# 7_ALARM.net
KiCad netlist of a schematic drawn in Altium Designer
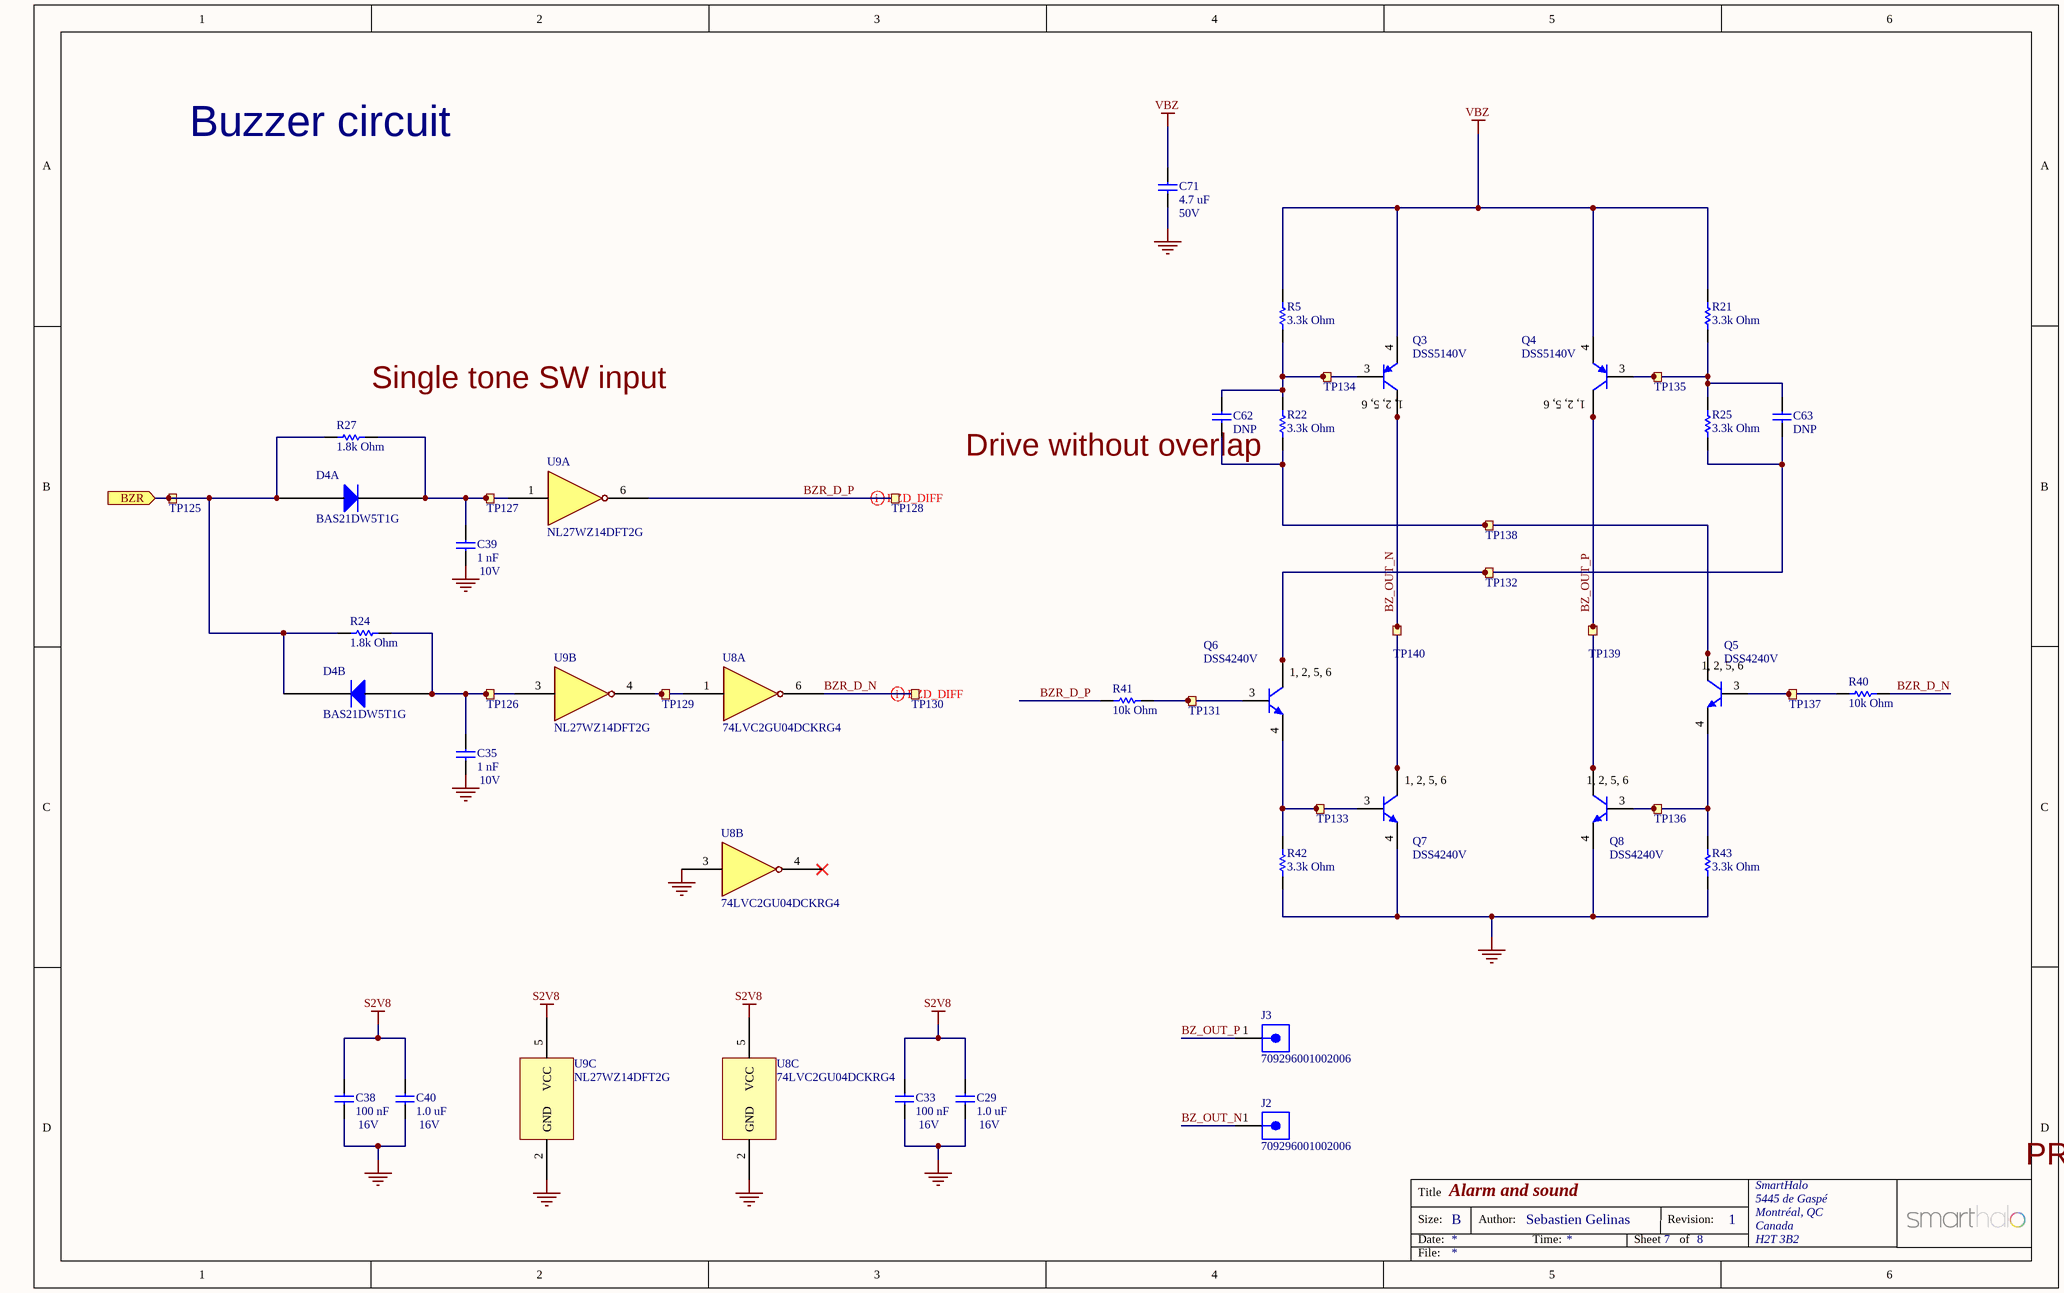
[diagram p0: 7_ALARM.SchDoc]

(export (version "E")
  (design (tool "Eeschema 10.0.6"))
  (components
    (comp (ref "C29")
      (value "1.0 uF")
      (footprint "Varitron_CAP0603")
      (description "1.0 uF 16V X7R 10% 0603 (1608 Metric)  SMD")
      (fields
        (field (name "TOLERANCE") "10%")
        (field (name "VOLTAGE RATING") "16V")
        (field (name "MANUFACTURER") "Samsung")
      )
      (libsource (lib "SmartHalo") (part "Varitron_CAP0603"))
    )
    (comp (ref "C33")
      (value "100 nF")
      (footprint "Varitron_CAP0402")
      (description "100 nF 16V X7R 10% 0402 (1005 Metric)  SMD")
      (fields
        (field (name "TOLERANCE") "10%")
        (field (name "VOLTAGE RATING") "16V")
        (field (name "MANUFACTURER") "Samsung")
      )
      (libsource (lib "SmartHalo") (part "Varitron_CAP0402"))
    )
    (comp (ref "C35")
      (value "1 nF")
      (footprint "Varitron_CAP0402")
      (description "1 nF 10V X7R 10% 0402 (1005 Metric)  SMD")
      (fields
        (field (name "TOLERANCE") "10%")
        (field (name "VOLTAGE RATING") "10V")
        (field (name "MANUFACTURER") "AVX")
      )
      (libsource (lib "SmartHalo") (part "Varitron_CAP0402"))
    )
    (comp (ref "C38")
      (value "100 nF")
      (footprint "Varitron_CAP0402")
      (description "100 nF 16V X7R 10% 0402 (1005 Metric)  SMD")
      (fields
        (field (name "TOLERANCE") "10%")
        (field (name "VOLTAGE RATING") "16V")
        (field (name "MANUFACTURER") "Samsung")
      )
      (libsource (lib "SmartHalo") (part "Varitron_CAP0402"))
    )
    (comp (ref "C39")
      (value "1 nF")
      (footprint "Varitron_CAP0402")
      (description "1 nF 10V X7R 10% 0402 (1005 Metric)  SMD")
      (fields
        (field (name "TOLERANCE") "10%")
        (field (name "VOLTAGE RATING") "10V")
        (field (name "MANUFACTURER") "AVX")
      )
      (libsource (lib "SmartHalo") (part "Varitron_CAP0402"))
    )
    (comp (ref "C40")
      (value "1.0 uF")
      (footprint "Varitron_CAP0603")
      (description "1.0 uF 16V X7R 10% 0603 (1608 Metric)  SMD")
      (fields
        (field (name "TOLERANCE") "10%")
        (field (name "VOLTAGE RATING") "16V")
        (field (name "MANUFACTURER") "Samsung")
      )
      (libsource (lib "SmartHalo") (part "Varitron_CAP0603"))
    )
    (comp (ref "C62")
      (value "DNP")
      (footprint "Varitron_CAP0402")
      (description "220 pF 50V X7R 10% 0402 (1005 Metric)  SMD")
      (fields (field (name "TOLERANCE") "10%"))
      (libsource (lib "SmartHalo") (part "Varitron_CAP0402"))
    )
    (comp (ref "C63")
      (value "DNP")
      (footprint "Varitron_CAP0402")
      (description "220 pF 50V X7R 10% 0402 (1005 Metric)  SMD")
      (fields (field (name "TOLERANCE") "10%"))
      (libsource (lib "SmartHalo") (part "Varitron_CAP0402"))
    )
    (comp (ref "C71")
      (value "4.7 uF")
      (footprint "Varitron_CAP0805")
      (description "4.7 uF 50V X5R 10% 0805 (2012 Metric)  SMD")
      (fields
        (field (name "TOLERANCE") "10%")
        (field (name "MANUFACTURER") "Samsung")
        (field (name "VOLTAGE RATING") "50V")
      )
      (libsource (lib "SmartHalo") (part "Varitron_CAP0805"))
    )
    (comp (ref "D4")
      (value "BAS21DW5T1G")
      (footprint "SC70-5")
      (description "High Voltage Switching Diode")
      (fields
        (field (name "MANUFACTURER") "ON Semiconductor")
        (field (name "SMARTHALO PART NUMBER") "630018-01")
      )
      (libsource (lib "SmartHalo") (part "BAS21DW5T1G"))
    )
    (comp (ref "J2")
      (value "709296001002006")
      (footprint "709296001002006")
      (description "Connector, Single Horizontal Contact, 2 x 2 mm")
      (fields (field (name "MANUFACTURER") "AVX") (field (name "SMARTHALO PART NUMBER") "630020-01"))
      (libsource (lib "SmartHalo") (part "709296001002006"))
    )
    (comp (ref "J3")
      (value "709296001002006")
      (footprint "709296001002006")
      (description "Connector, Single Horizontal Contact, 2 x 2 mm")
      (fields (field (name "MANUFACTURER") "AVX") (field (name "SMARTHALO PART NUMBER") "630020-01"))
      (libsource (lib "SmartHalo") (part "709296001002006"))
    )
    (comp (ref "Q3")
      (value "DSS5140V")
      (footprint "SOT563")
      (description "PNP SMT Transistor, Low VCESAT")
      (fields (field (name "MANUFACTURER") "Diodes Inc.") (field (name "SMARTHALO PART NUMBER") "630031-01"))
      (libsource (lib "SmartHalo") (part "DSS5140V"))
    )
    (comp (ref "Q4")
      (value "DSS5140V")
      (footprint "SOT563")
      (description "PNP SMT Transistor, Low VCESAT")
      (fields (field (name "MANUFACTURER") "Diodes Inc.") (field (name "SMARTHALO PART NUMBER") "630031-01"))
      (libsource (lib "SmartHalo") (part "DSS5140V"))
    )
    (comp (ref "Q5")
      (value "DSS4240V")
      (footprint "SOT563")
      (description "NPN SMT Transistor, Low VCESAT")
      (fields (field (name "MANUFACTURER") "Diodes Inc.") (field (name "SMARTHALO PART NUMBER") "630032-01"))
      (libsource (lib "SmartHalo") (part "DSS4240V"))
    )
    (comp (ref "Q6")
      (value "DSS4240V")
      (footprint "SOT563")
      (description "NPN SMT Transistor, Low VCESAT")
      (fields (field (name "MANUFACTURER") "Diodes Inc.") (field (name "SMARTHALO PART NUMBER") "630032-01"))
      (libsource (lib "SmartHalo") (part "DSS4240V"))
    )
    (comp (ref "Q7")
      (value "DSS4240V")
      (footprint "SOT563")
      (description "NPN SMT Transistor, Low VCESAT")
      (fields (field (name "MANUFACTURER") "Diodes Inc.") (field (name "SMARTHALO PART NUMBER") "630032-01"))
      (libsource (lib "SmartHalo") (part "DSS4240V"))
    )
    (comp (ref "Q8")
      (value "DSS4240V")
      (footprint "SOT563")
      (description "NPN SMT Transistor, Low VCESAT")
      (fields (field (name "MANUFACTURER") "Diodes Inc.") (field (name "SMARTHALO PART NUMBER") "630032-01"))
      (libsource (lib "SmartHalo") (part "DSS4240V"))
    )
    (comp (ref "R5")
      (value "3.3k Ohm")
      (footprint "Varitron_RES0402")
      (description "3k3 0.063W 5%  0402 (1005 Metric)  SMD")
      (fields (field (name "TOLERANCE") "5%") (field (name "POWER") "0.063"))
      (libsource (lib "SmartHalo") (part "Varitron_RES0402"))
    )
    (comp (ref "R21")
      (value "3.3k Ohm")
      (footprint "Varitron_RES0402")
      (description "3k3 0.063W 5%  0402 (1005 Metric)  SMD")
      (fields (field (name "TOLERANCE") "5%") (field (name "POWER") "0.063W"))
      (libsource (lib "SmartHalo") (part "Varitron_RES0402"))
    )
    (comp (ref "R22")
      (value "3.3k Ohm")
      (footprint "Varitron_RES0402")
      (description "3k3 0.063W 5%  0402 (1005 Metric)  SMD")
      (fields (field (name "TOLERANCE") "5%") (field (name "POWER") "0.063W"))
      (libsource (lib "SmartHalo") (part "Varitron_RES0402"))
    )
    (comp (ref "R24")
      (value "1.8k Ohm")
      (footprint "Varitron_RES0402")
      (description "1k8 0.063W 5%  0402 (1005 Metric)  SMD")
      (fields (field (name "TOLERANCE") "5%") (field (name "POWER") "0.063W"))
      (libsource (lib "SmartHalo") (part "Varitron_RES0402"))
    )
    (comp (ref "R25")
      (value "3.3k Ohm")
      (footprint "Varitron_RES0402")
      (description "3k3 0.063W 5%  0402 (1005 Metric)  SMD")
      (fields (field (name "TOLERANCE") "5%") (field (name "POWER") "0.063W"))
      (libsource (lib "SmartHalo") (part "Varitron_RES0402"))
    )
    (comp (ref "R27")
      (value "1.8k Ohm")
      (footprint "Varitron_RES0402")
      (description "1k8 0.063W 5%  0402 (1005 Metric)  SMD")
      (fields (field (name "TOLERANCE") "5%") (field (name "POWER") "0.063W"))
      (libsource (lib "SmartHalo") (part "Varitron_RES0402"))
    )
    (comp (ref "R40")
      (value "10k Ohm")
      (footprint "Varitron_RES0402")
      (description "10k 0.063W 5%  0402 (1005 Metric)  SMD")
      (fields (field (name "TOLERANCE") "5%") (field (name "POWER") "0.063W"))
      (libsource (lib "SmartHalo") (part "Varitron_RES0402"))
    )
    (comp (ref "R41")
      (value "10k Ohm")
      (footprint "Varitron_RES0402")
      (description "10k 0.063W 5%  0402 (1005 Metric)  SMD")
      (fields (field (name "TOLERANCE") "5%") (field (name "POWER") "0.063W"))
      (libsource (lib "SmartHalo") (part "Varitron_RES0402"))
    )
    (comp (ref "R42")
      (value "3.3k Ohm")
      (footprint "Varitron_RES0402")
      (description "3k3 0.063W 5%  0402 (1005 Metric)  SMD")
      (fields (field (name "TOLERANCE") "5%") (field (name "POWER") "0.063W"))
      (libsource (lib "SmartHalo") (part "Varitron_RES0402"))
    )
    (comp (ref "R43")
      (value "3.3k Ohm")
      (footprint "Varitron_RES0402")
      (description "3k3 0.063W 5%  0402 (1005 Metric)  SMD")
      (fields (field (name "TOLERANCE") "5%") (field (name "POWER") "0.063W"))
      (libsource (lib "SmartHalo") (part "Varitron_RES0402"))
    )
    (comp (ref "TP125")
      (value "TP125")
      (footprint "TESTPAD-TH-1_5mm")
      (description "Testpoint, through hole, 1.5mm")
      (libsource (lib "SmartHalo") (part "TESTPAD_TH_1_5MM"))
    )
    (comp (ref "TP126")
      (value "TP126")
      (footprint "TESTPAD-TH-35mils")
      (description "Testpoint, through hole, 35 mils")
      (libsource (lib "SmartHalo") (part "TESTPAD_TH_35mils"))
    )
    (comp (ref "TP127")
      (value "TP127")
      (footprint "TESTPAD-TH-35mils")
      (description "Testpoint, through hole, 35 mils")
      (libsource (lib "SmartHalo") (part "TESTPAD_TH_35mils"))
    )
    (comp (ref "TP128")
      (value "TP128")
      (footprint "TESTPAD-TH-35mils")
      (description "Testpoint, through hole, 35 mils")
      (libsource (lib "SmartHalo") (part "TESTPAD_TH_35mils"))
    )
    (comp (ref "TP129")
      (value "TP129")
      (footprint "TESTPAD-TH-35mils")
      (description "Testpoint, through hole, 35 mils")
      (libsource (lib "SmartHalo") (part "TESTPAD_TH_35mils"))
    )
    (comp (ref "TP130")
      (value "TP130")
      (footprint "TESTPAD-TH-35mils")
      (description "Testpoint, through hole, 35 mils")
      (libsource (lib "SmartHalo") (part "TESTPAD_TH_35mils"))
    )
    (comp (ref "TP131")
      (value "TP131")
      (footprint "TESTPAD-TH-35mils")
      (description "Testpoint, through hole, 35 mils")
      (libsource (lib "SmartHalo") (part "TESTPAD_TH_35mils"))
    )
    (comp (ref "TP132")
      (value "TP132")
      (footprint "TESTPAD-TH-35mils")
      (description "Testpoint, through hole, 35 mils")
      (libsource (lib "SmartHalo") (part "TESTPAD_TH_35mils"))
    )
    (comp (ref "TP133")
      (value "TP133")
      (footprint "TESTPAD-TH-35mils")
      (description "Testpoint, through hole, 35 mils")
      (libsource (lib "SmartHalo") (part "TESTPAD_TH_35mils"))
    )
    (comp (ref "TP134")
      (value "TP134")
      (footprint "TESTPAD-TH-35mils")
      (description "Testpoint, through hole, 35 mils")
      (libsource (lib "SmartHalo") (part "TESTPAD_TH_35mils"))
    )
    (comp (ref "TP135")
      (value "TP135")
      (footprint "TESTPAD-TH-35mils")
      (description "Testpoint, through hole, 35 mils")
      (libsource (lib "SmartHalo") (part "TESTPAD_TH_35mils"))
    )
    (comp (ref "TP136")
      (value "TP136")
      (footprint "TESTPAD-TH-35mils")
      (description "Testpoint, through hole, 35 mils")
      (libsource (lib "SmartHalo") (part "TESTPAD_TH_35mils"))
    )
    (comp (ref "TP137")
      (value "TP137")
      (footprint "TESTPAD-TH-35mils")
      (description "Testpoint, through hole, 35 mils")
      (libsource (lib "SmartHalo") (part "TESTPAD_TH_35mils"))
    )
    (comp (ref "TP138")
      (value "TP138")
      (footprint "TESTPAD-TH-35mils")
      (description "Testpoint, through hole, 35 mils")
      (libsource (lib "SmartHalo") (part "TESTPAD_TH_35mils"))
    )
    (comp (ref "TP139")
      (value "TP139")
      (footprint "TESTPAD-TH-1_5mm")
      (description "Testpoint, through hole, 1.5mm")
      (libsource (lib "") (part "TESTPAD_TH_1_5MM_1"))
    )
    (comp (ref "TP140")
      (value "TP140")
      (footprint "TESTPAD-TH-1_5mm")
      (description "Testpoint, through hole, 1.5mm")
      (libsource (lib "") (part "TESTPAD_TH_1_5MM_1"))
    )
    (comp (ref "U8")
      (value "74LVC2GU04DCKRG4")
      (footprint "SOT363_SC70_6")
      (description "Dual Inverter Gate")
      (fields
        (field (name "MANUFACTURER") "Texas Instruments")
        (field (name "SMARTHALO PART NUMBER") "630057-01")
      )
      (libsource (lib "SmartHalo") (part "74LVC2GU04DCKRG4"))
    )
    (comp (ref "U9")
      (value "NL27WZ14DFT2G")
      (footprint "SOT363_SC70_6")
      (description "IC Dual Inverter with Schmitt Trigger Inputs")
      (fields
        (field (name "MANUFACTURER") "ON Semiconductor")
        (field (name "SMARTHALO PART NUMBER") "630058-01")
      )
      (libsource (lib "SmartHalo") (part "NL27WZ14DFT2G"))
    )
  )
  (nets
    (net (code "1") (name "/BZR") (class "Default")
      (node (ref "D4") (pin "1") (pinfunction "Anode_1") (pintype "passive"))
      (node (ref "D4") (pin "4") (pinfunction "Cathode_4") (pintype "passive"))
      (node (ref "R24") (pin "2") (pinfunction "2_2") (pintype "passive"))
      (node (ref "R27") (pin "2") (pinfunction "2_2") (pintype "passive"))
      (node (ref "TP125") (pin "1") (pinfunction "1_1") (pintype "passive"))
    )
    (net (code "2") (name "/BZR_D_N") (class "Default")
      (node (ref "R40") (pin "2") (pinfunction "2_2") (pintype "passive"))
      (node (ref "TP130") (pin "1") (pinfunction "1_1") (pintype "passive"))
      (node (ref "U8") (pin "6") (pinfunction "6_6") (pintype "passive"))
    )
    (net (code "3") (name "/BZR_D_P") (class "Default")
      (node (ref "R41") (pin "2") (pinfunction "2_2") (pintype "passive"))
      (node (ref "TP128") (pin "1") (pinfunction "1_1") (pintype "passive"))
      (node (ref "U9") (pin "6") (pinfunction "6_6") (pintype "passive"))
    )
    (net (code "4") (name "/BZ_OUT_N") (class "Default")
      (node (ref "J2") (pin "1") (pinfunction "1_1") (pintype "passive"))
      (node (ref "Q3") (pin "1") (pinfunction "C_1") (pintype "passive"))
      (node (ref "Q3") (pin "2") (pinfunction "C_2") (pintype "passive"))
      (node (ref "Q3") (pin "5") (pinfunction "C_5") (pintype "passive"))
      (node (ref "Q3") (pin "6") (pinfunction "C_6") (pintype "passive"))
      (node (ref "Q7") (pin "1") (pinfunction "C_1") (pintype "passive"))
      (node (ref "Q7") (pin "2") (pinfunction "C_2") (pintype "passive"))
      (node (ref "Q7") (pin "5") (pinfunction "C_5") (pintype "passive"))
      (node (ref "Q7") (pin "6") (pinfunction "C_6") (pintype "passive"))
      (node (ref "TP140") (pin "1") (pinfunction "1_1") (pintype "passive"))
    )
    (net (code "5") (name "/BZ_OUT_P") (class "Default")
      (node (ref "J3") (pin "1") (pinfunction "1_1") (pintype "passive"))
      (node (ref "Q4") (pin "1") (pinfunction "C_1") (pintype "passive"))
      (node (ref "Q4") (pin "2") (pinfunction "C_2") (pintype "passive"))
      (node (ref "Q4") (pin "5") (pinfunction "C_5") (pintype "passive"))
      (node (ref "Q4") (pin "6") (pinfunction "C_6") (pintype "passive"))
      (node (ref "Q8") (pin "1") (pinfunction "C_1") (pintype "passive"))
      (node (ref "Q8") (pin "2") (pinfunction "C_2") (pintype "passive"))
      (node (ref "Q8") (pin "5") (pinfunction "C_5") (pintype "passive"))
      (node (ref "Q8") (pin "6") (pinfunction "C_6") (pintype "passive"))
      (node (ref "TP139") (pin "1") (pinfunction "1_1") (pintype "passive"))
    )
    (net (code "6") (name "GND") (class "Default")
      (node (ref "C29") (pin "2") (pinfunction "2_2") (pintype "passive"))
      (node (ref "C33") (pin "2") (pinfunction "2_2") (pintype "passive"))
      (node (ref "C35") (pin "2") (pinfunction "2_2") (pintype "passive"))
      (node (ref "C38") (pin "2") (pinfunction "2_2") (pintype "passive"))
      (node (ref "C39") (pin "2") (pinfunction "2_2") (pintype "passive"))
      (node (ref "C40") (pin "2") (pinfunction "2_2") (pintype "passive"))
      (node (ref "C71") (pin "2") (pinfunction "2_2") (pintype "passive"))
      (node (ref "Q7") (pin "4") (pinfunction "E_4") (pintype "passive"))
      (node (ref "Q8") (pin "4") (pinfunction "E_4") (pintype "passive"))
      (node (ref "R42") (pin "2") (pinfunction "2_2") (pintype "passive"))
      (node (ref "R43") (pin "1") (pinfunction "1_1") (pintype "passive"))
      (node (ref "U8") (pin "2") (pinfunction "GND_2") (pintype "passive"))
      (node (ref "U8") (pin "3") (pinfunction "3_3") (pintype "passive"))
      (node (ref "U9") (pin "2") (pinfunction "GND_2") (pintype "passive"))
    )
    (net (code "7") (name "Net-(C62-Pad1)") (class "Default")
      (node (ref "C62") (pin "1") (pinfunction "1_1") (pintype "passive"))
      (node (ref "Q5") (pin "1") (pinfunction "C_1") (pintype "passive"))
      (node (ref "Q5") (pin "2") (pinfunction "C_2") (pintype "passive"))
      (node (ref "Q5") (pin "5") (pinfunction "C_5") (pintype "passive"))
      (node (ref "Q5") (pin "6") (pinfunction "C_6") (pintype "passive"))
      (node (ref "R22") (pin "1") (pinfunction "1_1") (pintype "passive"))
      (node (ref "TP138") (pin "1") (pinfunction "1_1") (pintype "passive"))
    )
    (net (code "8") (name "Net-(C63-Pad1)") (class "Default")
      (node (ref "C63") (pin "1") (pinfunction "1_1") (pintype "passive"))
      (node (ref "Q6") (pin "1") (pinfunction "C_1") (pintype "passive"))
      (node (ref "Q6") (pin "2") (pinfunction "C_2") (pintype "passive"))
      (node (ref "Q6") (pin "5") (pinfunction "C_5") (pintype "passive"))
      (node (ref "Q6") (pin "6") (pinfunction "C_6") (pintype "passive"))
      (node (ref "R25") (pin "1") (pinfunction "1_1") (pintype "passive"))
      (node (ref "TP132") (pin "1") (pinfunction "1_1") (pintype "passive"))
    )
    (net (code "9") (name "Net-(D4A-Cathode)") (class "Default")
      (node (ref "C39") (pin "1") (pinfunction "1_1") (pintype "passive"))
      (node (ref "D4") (pin "5") (pinfunction "Cathode_5") (pintype "passive"))
      (node (ref "R27") (pin "1") (pinfunction "1_1") (pintype "passive"))
      (node (ref "TP127") (pin "1") (pinfunction "1_1") (pintype "passive"))
      (node (ref "U9") (pin "1") (pinfunction "1_1") (pintype "passive"))
    )
    (net (code "10") (name "Net-(D4B-Anode)") (class "Default")
      (node (ref "C35") (pin "1") (pinfunction "1_1") (pintype "passive"))
      (node (ref "D4") (pin "3") (pinfunction "Anode_3") (pintype "passive"))
      (node (ref "R24") (pin "1") (pinfunction "1_1") (pintype "passive"))
      (node (ref "TP126") (pin "1") (pinfunction "1_1") (pintype "passive"))
      (node (ref "U9") (pin "3") (pinfunction "3_3") (pintype "passive"))
    )
    (net (code "11") (name "Net-(Q3-B)") (class "Default")
      (node (ref "C62") (pin "2") (pinfunction "2_2") (pintype "passive"))
      (node (ref "Q3") (pin "3") (pinfunction "B_3") (pintype "passive"))
      (node (ref "R22") (pin "2") (pinfunction "2_2") (pintype "passive"))
      (node (ref "R5") (pin "1") (pinfunction "1_1") (pintype "passive"))
      (node (ref "TP134") (pin "1") (pinfunction "1_1") (pintype "passive"))
    )
    (net (code "12") (name "Net-(Q4-B)") (class "Default")
      (node (ref "C63") (pin "2") (pinfunction "2_2") (pintype "passive"))
      (node (ref "Q4") (pin "3") (pinfunction "B_3") (pintype "passive"))
      (node (ref "R21") (pin "1") (pinfunction "1_1") (pintype "passive"))
      (node (ref "R25") (pin "2") (pinfunction "2_2") (pintype "passive"))
      (node (ref "TP135") (pin "1") (pinfunction "1_1") (pintype "passive"))
    )
    (net (code "13") (name "Net-(Q5-B)") (class "Default")
      (node (ref "Q5") (pin "3") (pinfunction "B_3") (pintype "passive"))
      (node (ref "R40") (pin "1") (pinfunction "1_1") (pintype "passive"))
      (node (ref "TP137") (pin "1") (pinfunction "1_1") (pintype "passive"))
    )
    (net (code "14") (name "Net-(Q5-E)") (class "Default")
      (node (ref "Q5") (pin "4") (pinfunction "E_4") (pintype "passive"))
      (node (ref "Q8") (pin "3") (pinfunction "B_3") (pintype "passive"))
      (node (ref "R43") (pin "2") (pinfunction "2_2") (pintype "passive"))
      (node (ref "TP136") (pin "1") (pinfunction "1_1") (pintype "passive"))
    )
    (net (code "15") (name "Net-(Q6-B)") (class "Default")
      (node (ref "Q6") (pin "3") (pinfunction "B_3") (pintype "passive"))
      (node (ref "R41") (pin "1") (pinfunction "1_1") (pintype "passive"))
      (node (ref "TP131") (pin "1") (pinfunction "1_1") (pintype "passive"))
    )
    (net (code "16") (name "Net-(Q6-E)") (class "Default")
      (node (ref "Q6") (pin "4") (pinfunction "E_4") (pintype "passive"))
      (node (ref "Q7") (pin "3") (pinfunction "B_3") (pintype "passive"))
      (node (ref "R42") (pin "1") (pinfunction "1_1") (pintype "passive"))
      (node (ref "TP133") (pin "1") (pinfunction "1_1") (pintype "passive"))
    )
    (net (code "17") (name "Net-(TP129-Pad1)") (class "Default")
      (node (ref "TP129") (pin "1") (pinfunction "1_1") (pintype "passive"))
      (node (ref "U8") (pin "1") (pinfunction "1_1") (pintype "passive"))
      (node (ref "U9") (pin "4") (pinfunction "4_4") (pintype "passive"))
    )
    (net (code "18") (name "S2V8") (class "Default")
      (node (ref "C29") (pin "1") (pinfunction "1_1") (pintype "passive"))
      (node (ref "C33") (pin "1") (pinfunction "1_1") (pintype "passive"))
      (node (ref "C38") (pin "1") (pinfunction "1_1") (pintype "passive"))
      (node (ref "C40") (pin "1") (pinfunction "1_1") (pintype "passive"))
      (node (ref "U8") (pin "5") (pinfunction "VCC_5") (pintype "passive"))
      (node (ref "U9") (pin "5") (pinfunction "VCC_5") (pintype "passive"))
    )
    (net (code "19") (name "VBZ") (class "Default")
      (node (ref "C71") (pin "1") (pinfunction "1_1") (pintype "passive"))
      (node (ref "Q3") (pin "4") (pinfunction "E_4") (pintype "passive"))
      (node (ref "Q4") (pin "4") (pinfunction "E_4") (pintype "passive"))
      (node (ref "R21") (pin "2") (pinfunction "2_2") (pintype "passive"))
      (node (ref "R5") (pin "2") (pinfunction "2_2") (pintype "passive"))
    )
    (net (code "20") (name "unconnected-(D4-Pad2)") (class "Default")
      (node (ref "D4") (pin "2") (pinfunction "2_2") (pintype "passive"))
    )
    (net (code "21") (name "unconnected-(U8-Pad4)") (class "Default")
      (node (ref "U8") (pin "4") (pinfunction "4_4") (pintype "passive+no_connect"))
    )
  )
)
